# 8600ACBIS.net
KiCad netlist of a schematic drawn in EAGLE
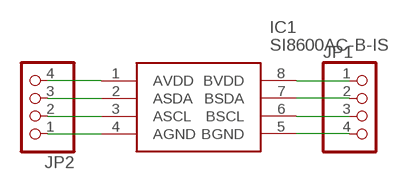
[diagram p0: schematic, sheet 1]

(export (version "E")
  (design (tool "Eeschema 10.0.6"))
  (components
    (comp (ref "IC1")
      (value "SI8600AC-B-IS")
      (footprint "eagle-import:SOIC127P600X175-8N")
      (fields (field (name "ARROW_PART_NUMBER") "Si8600AC-B-IS") (field (name "RS_PART_NUMBER") "1689848"))
      (libsource (lib "eagle-import") (part "SI8600AC-B-IS"))
    )
    (comp (ref "JP1")
      (value "PINHD-1X4")
      (footprint "eagle-import:1X04")
      (libsource (lib "eagle-import") (part "PINHD-1X4"))
    )
    (comp (ref "JP2")
      (value "PINHD-1X4")
      (footprint "eagle-import:1X04")
      (libsource (lib "eagle-import") (part "PINHD-1X4"))
    )
  )
  (nets
    (net (code "1") (name "Net-(IC1-AGND)") (class "Default")
      (node (ref "IC1") (pin "4") (pinfunction "AGND_4") (pintype "power_in"))
      (node (ref "JP2") (pin "1") (pinfunction "1_1") (pintype "passive"))
    )
    (net (code "2") (name "Net-(IC1-ASCL)") (class "Default")
      (node (ref "IC1") (pin "3") (pinfunction "ASCL_3") (pintype "bidirectional"))
      (node (ref "JP2") (pin "2") (pinfunction "2_2") (pintype "passive"))
    )
    (net (code "3") (name "Net-(IC1-ASDA)") (class "Default")
      (node (ref "IC1") (pin "2") (pinfunction "ASDA_2") (pintype "bidirectional"))
      (node (ref "JP2") (pin "3") (pinfunction "3_3") (pintype "passive"))
    )
    (net (code "4") (name "Net-(IC1-AVDD)") (class "Default")
      (node (ref "IC1") (pin "1") (pinfunction "AVDD_1") (pintype "power_in"))
      (node (ref "JP2") (pin "4") (pinfunction "4_4") (pintype "passive"))
    )
    (net (code "5") (name "Net-(IC1-BGND)") (class "Default")
      (node (ref "IC1") (pin "5") (pinfunction "BGND_5") (pintype "power_in"))
      (node (ref "JP1") (pin "4") (pinfunction "4_4") (pintype "passive"))
    )
    (net (code "6") (name "Net-(IC1-BSCL)") (class "Default")
      (node (ref "IC1") (pin "6") (pinfunction "BSCL_6") (pintype "bidirectional"))
      (node (ref "JP1") (pin "3") (pinfunction "3_3") (pintype "passive"))
    )
    (net (code "7") (name "Net-(IC1-BSDA)") (class "Default")
      (node (ref "IC1") (pin "7") (pinfunction "BSDA_7") (pintype "bidirectional"))
      (node (ref "JP1") (pin "2") (pinfunction "2_2") (pintype "passive"))
    )
    (net (code "8") (name "Net-(IC1-BVDD)") (class "Default")
      (node (ref "IC1") (pin "8") (pinfunction "BVDD_8") (pintype "power_in"))
      (node (ref "JP1") (pin "1") (pinfunction "1_1") (pintype "passive"))
    )
  )
)
